# Microcontroller_Stage.net
KiCad netlist of a schematic drawn in Altium Designer
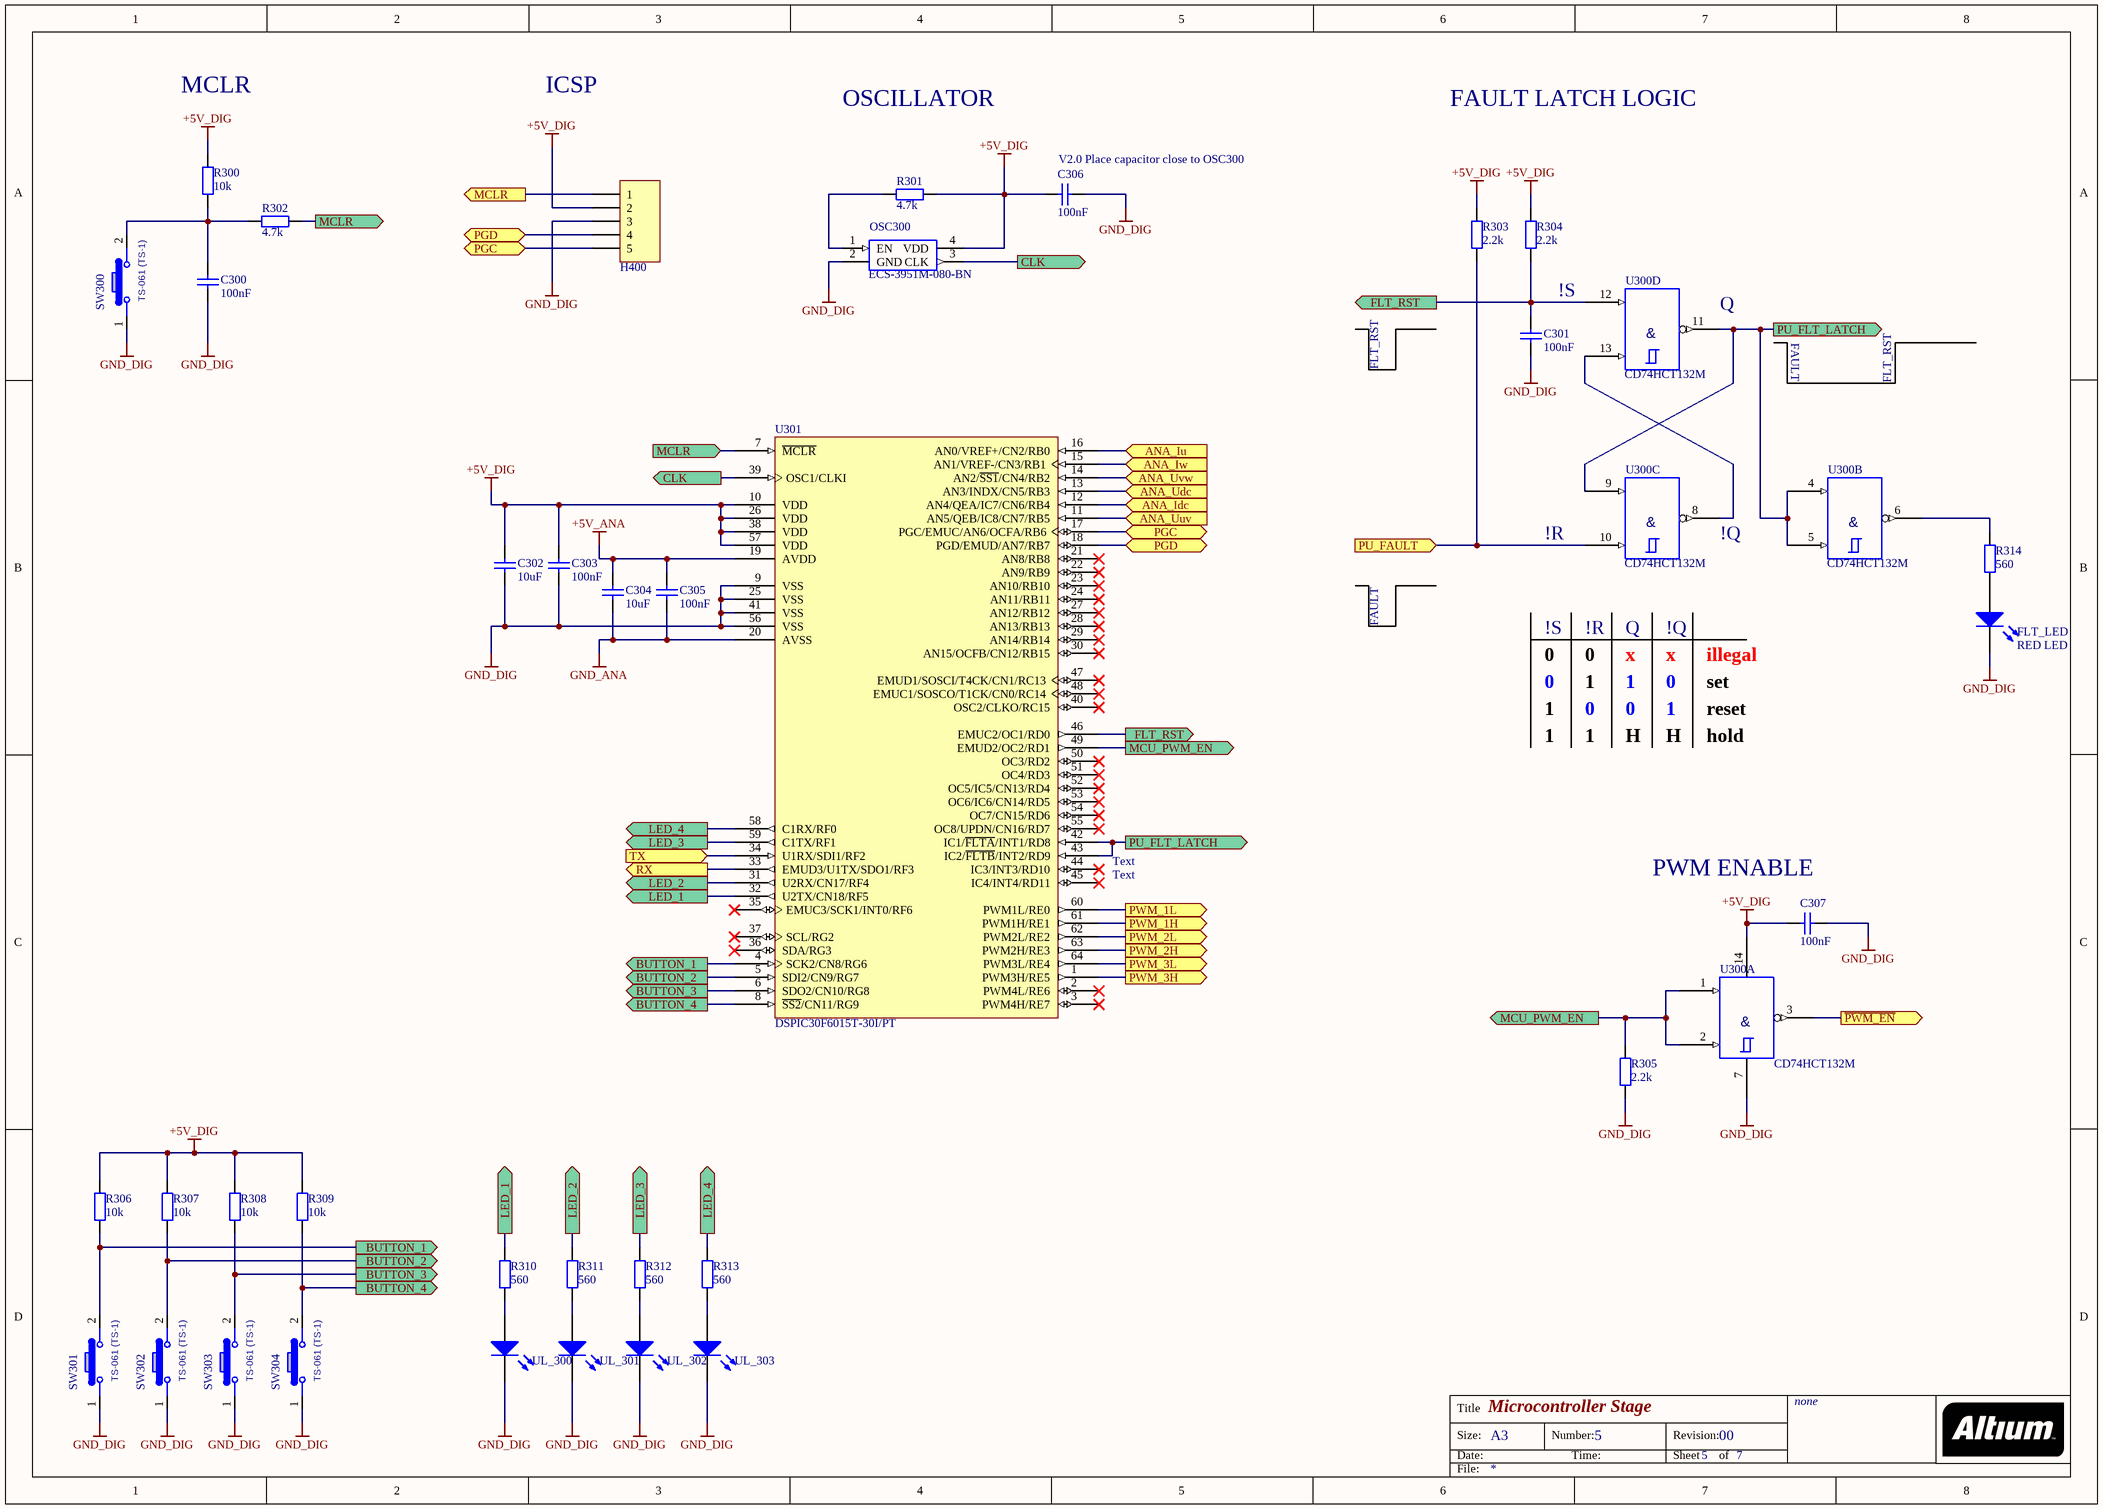
[diagram p0: Microcontroller Stage.SchDoc]

(export (version "E")
  (design (tool "Eeschema 10.0.6"))
  (components
    (comp (ref "C300")
      (value "100nF")
      (footprint "1206_REFLOW")
      (fields (field (name "Comment") "Cap 1206"))
      (libsource (lib "Capacitors") (part "Cap 1206"))
    )
    (comp (ref "C301")
      (value "100nF")
      (footprint "1206_REFLOW")
      (fields (field (name "Comment") "Cap 1206"))
      (libsource (lib "Capacitors") (part "Cap 1206"))
    )
    (comp (ref "C302")
      (value "10uF")
      (footprint "1206_REFLOW")
      (fields (field (name "Comment") "Cap 1206"))
      (libsource (lib "Capacitors") (part "Cap 1206"))
    )
    (comp (ref "C303")
      (value "100nF")
      (footprint "1206_REFLOW")
      (fields (field (name "Comment") "Cap 1206"))
      (libsource (lib "Capacitors") (part "Cap 1206"))
    )
    (comp (ref "C304")
      (value "10uF")
      (footprint "1206_REFLOW")
      (fields (field (name "Comment") "Cap 1206"))
      (libsource (lib "Capacitors") (part "Cap 1206"))
    )
    (comp (ref "C305")
      (value "100nF")
      (footprint "1206_REFLOW")
      (fields (field (name "Comment") "Cap 1206"))
      (libsource (lib "Capacitors") (part "Cap 1206"))
    )
    (comp (ref "C306")
      (value "100nF")
      (footprint "1206_REFLOW")
      (fields (field (name "Comment") "Cap 1206"))
      (libsource (lib "Capacitors") (part "Cap 1206"))
    )
    (comp (ref "C307")
      (value "100nF")
      (footprint "1206_REFLOW")
      (fields (field (name "Comment") "Cap 1206"))
      (libsource (lib "Capacitors") (part "Cap 1206"))
    )
    (comp (ref "FLT_LED") (value "RED LED") (footprint "LED_1206") (libsource (lib "LED") (part "LED")))
    (comp (ref "H400")
      (value "HEADER X5")
      (footprint "SIP5")
      (libsource (lib "Connector") (part "HEADER X5"))
    )
    (comp (ref "OSC300")
      (value "ECS-3951M-080-BN")
      (footprint "OSC7X5")
      (description "ESC-3951M-80-BN 8Mhz")
      (fields (field (name "MFRR PART NO.") "ECS-3951M-080-BN-TR") (field (name "Comment") "ESC-3951M-80-BN"))
      (libsource (lib "Oscillator") (part "ESC-3951M-80-BN"))
    )
    (comp (ref "R300")
      (value "10k")
      (footprint "1206_REFLOW")
      (fields (field (name "Comment") "RES"))
      (libsource (lib "Resistor") (part "RES 1"))
    )
    (comp (ref "R301")
      (value "4.7k")
      (footprint "1206_REFLOW")
      (fields (field (name "Comment") "RES"))
      (libsource (lib "") (part "RES 1_2"))
    )
    (comp (ref "R302")
      (value "4.7k")
      (footprint "1206_REFLOW")
      (fields (field (name "Comment") "RES"))
      (libsource (lib "") (part "RES 1_3"))
    )
    (comp (ref "R303")
      (value "2.2k")
      (footprint "1206_REFLOW")
      (fields (field (name "Comment") "RES"))
      (libsource (lib "Resistor") (part "RES 1"))
    )
    (comp (ref "R304")
      (value "2.2k")
      (footprint "1206_REFLOW")
      (fields (field (name "Comment") "RES"))
      (libsource (lib "Resistor") (part "RES 1"))
    )
    (comp (ref "R305")
      (value "2.2k")
      (footprint "1206_REFLOW")
      (fields (field (name "Comment") "RES"))
      (libsource (lib "Resistor") (part "RES 1"))
    )
    (comp (ref "R306")
      (value "10k")
      (footprint "1206_REFLOW")
      (fields (field (name "Comment") "RES"))
      (libsource (lib "Resistor") (part "RES 1"))
    )
    (comp (ref "R307")
      (value "10k")
      (footprint "1206_REFLOW")
      (fields (field (name "Comment") "RES"))
      (libsource (lib "Resistor") (part "RES 1"))
    )
    (comp (ref "R308")
      (value "10k")
      (footprint "1206_REFLOW")
      (fields (field (name "Comment") "RES"))
      (libsource (lib "Resistor") (part "RES 1"))
    )
    (comp (ref "R309")
      (value "10k")
      (footprint "1206_REFLOW")
      (fields (field (name "Comment") "RES"))
      (libsource (lib "Resistor") (part "RES 1"))
    )
    (comp (ref "R310")
      (value "560")
      (footprint "1206_REFLOW")
      (fields (field (name "Comment") "RES"))
      (libsource (lib "") (part "RES 1_1"))
    )
    (comp (ref "R311")
      (value "560")
      (footprint "1206_REFLOW")
      (fields (field (name "Comment") "RES"))
      (libsource (lib "") (part "RES 1_1"))
    )
    (comp (ref "R312")
      (value "560")
      (footprint "1206_REFLOW")
      (fields (field (name "Comment") "RES"))
      (libsource (lib "") (part "RES 1_1"))
    )
    (comp (ref "R313")
      (value "560")
      (footprint "1206_REFLOW")
      (fields (field (name "Comment") "RES"))
      (libsource (lib "") (part "RES 1_1"))
    )
    (comp (ref "R314")
      (value "560")
      (footprint "1206_REFLOW")
      (fields (field (name "Comment") "RES"))
      (libsource (lib "") (part "RES 1_1"))
    )
    (comp (ref "SW300")
      (value "TS-061 (TS-1)")
      (footprint "BUTTON")
      (description "BUTTON")
      (libsource (lib "Button") (part "TS-061 (TS-1)"))
    )
    (comp (ref "SW301")
      (value "TS-061 (TS-1)")
      (footprint "BUTTON")
      (description "BUTTON")
      (libsource (lib "Button") (part "TS-061 (TS-1)"))
    )
    (comp (ref "SW302")
      (value "TS-061 (TS-1)")
      (footprint "BUTTON")
      (description "BUTTON")
      (libsource (lib "Button") (part "TS-061 (TS-1)"))
    )
    (comp (ref "SW303")
      (value "TS-061 (TS-1)")
      (footprint "BUTTON")
      (description "BUTTON")
      (libsource (lib "Button") (part "TS-061 (TS-1)"))
    )
    (comp (ref "SW304")
      (value "TS-061 (TS-1)")
      (footprint "BUTTON")
      (description "BUTTON")
      (libsource (lib "Button") (part "TS-061 (TS-1)"))
    )
    (comp (ref "U300")
      (value "CD74HCT132M")
      (footprint "SO14")
      (libsource (lib "Logic") (part "CD74HCT132M"))
    )
    (comp (ref "U301")
      (value "DSPIC30F6015T-30I/PT")
      (footprint "TQFP-PT64_N")
      (fields (field (name "PUBLISHER") "Altium Limited"))
      (libsource (lib "Microchip DSC 16-Bit dsPIC30F") (part "DSPIC30F6015T-30I/PT"))
    )
    (comp (ref "UL_300") (value "YELLOW LED") (footprint "LED_1206") (libsource (lib "LED") (part "LED")))
    (comp (ref "UL_301") (value "YELLOW LED") (footprint "LED_1206") (libsource (lib "LED") (part "LED")))
    (comp (ref "UL_302") (value "YELLOW LED") (footprint "LED_1206") (libsource (lib "LED") (part "LED")))
    (comp (ref "UL_303") (value "YELLOW LED") (footprint "LED_1206") (libsource (lib "LED") (part "LED")))
  )
  (nets
    (net (code "1") (name "+5V_ANA") (class "Default")
      (node (ref "C304") (pin "2") (pinfunction "2_2") (pintype "passive"))
      (node (ref "C305") (pin "2") (pinfunction "2_2") (pintype "passive"))
      (node (ref "U301") (pin "19") (pinfunction "AVDD_19") (pintype "power_in"))
    )
    (net (code "2") (name "+5V_DIG") (class "Default")
      (node (ref "C302") (pin "2") (pinfunction "2_2") (pintype "passive"))
      (node (ref "C303") (pin "2") (pinfunction "2_2") (pintype "passive"))
      (node (ref "C306") (pin "1") (pinfunction "1_1") (pintype "passive"))
      (node (ref "C307") (pin "2") (pinfunction "2_2") (pintype "passive"))
      (node (ref "H400") (pin "2") (pinfunction "2_2") (pintype "passive"))
      (node (ref "OSC300") (pin "4") (pinfunction "VDD_4") (pintype "power_in"))
      (node (ref "R300") (pin "1") (pinfunction "1_1") (pintype "passive"))
      (node (ref "R301") (pin "1") (pinfunction "1_1") (pintype "passive"))
      (node (ref "R303") (pin "1") (pinfunction "1_1") (pintype "passive"))
      (node (ref "R304") (pin "1") (pinfunction "1_1") (pintype "passive"))
      (node (ref "R306") (pin "1") (pinfunction "1_1") (pintype "passive"))
      (node (ref "R307") (pin "1") (pinfunction "1_1") (pintype "passive"))
      (node (ref "R308") (pin "1") (pinfunction "1_1") (pintype "passive"))
      (node (ref "R309") (pin "1") (pinfunction "1_1") (pintype "passive"))
      (node (ref "U300") (pin "14") (pinfunction "Vcc_14") (pintype "power_in"))
      (node (ref "U301") (pin "10") (pinfunction "VDD_10") (pintype "power_in"))
      (node (ref "U301") (pin "26") (pinfunction "VDD_26") (pintype "power_in"))
      (node (ref "U301") (pin "38") (pinfunction "VDD_38") (pintype "power_in"))
      (node (ref "U301") (pin "57") (pinfunction "VDD_57") (pintype "power_in"))
    )
    (net (code "3") (name "/ANA_Idc") (class "Default")
      (node (ref "U301") (pin "12") (pinfunction "AN4/QEA/IC7/CN6/RB4_12") (pintype "input"))
    )
    (net (code "4") (name "/ANA_Iu") (class "Default")
      (node (ref "U301") (pin "16") (pinfunction "AN0/VREF+/CN2/RB0_16") (pintype "input"))
    )
    (net (code "5") (name "/ANA_Iw") (class "Default")
      (node (ref "U301") (pin "15") (pinfunction "AN1/VREF-/CN3/RB1_15") (pintype "input"))
    )
    (net (code "6") (name "/ANA_Udc") (class "Default")
      (node (ref "U301") (pin "13") (pinfunction "AN3/INDX/CN5/RB3_13") (pintype "input"))
    )
    (net (code "7") (name "/ANA_Uuv") (class "Default")
      (node (ref "U301") (pin "11") (pinfunction "AN5/QEB/IC8/CN7/RB5_11") (pintype "input"))
    )
    (net (code "8") (name "/ANA_Uvw") (class "Default")
      (node (ref "U301") (pin "14") (pinfunction "AN2/~{SS1}/CN4/RB2_14") (pintype "input"))
    )
    (net (code "9") (name "/BUTTON_1") (class "Default")
      (node (ref "R306") (pin "2") (pinfunction "2_2") (pintype "passive"))
      (node (ref "SW301") (pin "2") (pintype "passive"))
      (node (ref "U301") (pin "4") (pinfunction "SCK2/CN8/RG6_4") (pintype "input"))
    )
    (net (code "10") (name "/BUTTON_2") (class "Default")
      (node (ref "R307") (pin "2") (pinfunction "2_2") (pintype "passive"))
      (node (ref "SW302") (pin "2") (pintype "passive"))
      (node (ref "U301") (pin "5") (pinfunction "SDI2/CN9/RG7_5") (pintype "input"))
    )
    (net (code "11") (name "/BUTTON_3") (class "Default")
      (node (ref "R308") (pin "2") (pinfunction "2_2") (pintype "passive"))
      (node (ref "SW303") (pin "2") (pintype "passive"))
      (node (ref "U301") (pin "6") (pinfunction "SDO2/CN10/RG8_6") (pintype "input"))
    )
    (net (code "12") (name "/BUTTON_4") (class "Default")
      (node (ref "R309") (pin "2") (pinfunction "2_2") (pintype "passive"))
      (node (ref "SW304") (pin "2") (pintype "passive"))
      (node (ref "U301") (pin "8") (pinfunction "~{SS2}/CN11/RG9_8") (pintype "input"))
    )
    (net (code "13") (name "/CLK") (class "Default")
      (node (ref "OSC300") (pin "3") (pinfunction "CLK_3") (pintype "output"))
      (node (ref "U301") (pin "39") (pinfunction "OSC1/CLKI_39") (pintype "input"))
    )
    (net (code "14") (name "/FLT_RST") (class "Default")
      (node (ref "C301") (pin "2") (pinfunction "2_2") (pintype "passive"))
      (node (ref "R304") (pin "2") (pinfunction "2_2") (pintype "passive"))
      (node (ref "U300") (pin "12") (pinfunction "4A_12") (pintype "input"))
      (node (ref "U301") (pin "46") (pinfunction "EMUC2/OC1/RD0_46") (pintype "output"))
    )
    (net (code "15") (name "/LED_1") (class "Default")
      (node (ref "R310") (pin "2") (pinfunction "2_2") (pintype "passive"))
      (node (ref "U301") (pin "32") (pinfunction "U2TX/CN18/RF5_32") (pintype "output"))
    )
    (net (code "16") (name "/LED_2") (class "Default")
      (node (ref "R311") (pin "2") (pinfunction "2_2") (pintype "passive"))
      (node (ref "U301") (pin "31") (pinfunction "U2RX/CN17/RF4_31") (pintype "output"))
    )
    (net (code "17") (name "/LED_3") (class "Default")
      (node (ref "R312") (pin "2") (pinfunction "2_2") (pintype "passive"))
      (node (ref "U301") (pin "59") (pinfunction "C1TX/RF1_59") (pintype "output"))
    )
    (net (code "18") (name "/LED_4") (class "Default")
      (node (ref "R313") (pin "2") (pinfunction "2_2") (pintype "passive"))
      (node (ref "U301") (pin "58") (pinfunction "C1RX/RF0_58") (pintype "output"))
    )
    (net (code "19") (name "/MCLR") (class "Default")
      (node (ref "H400") (pin "1") (pinfunction "1_1") (pintype "passive"))
      (node (ref "R302") (pin "2") (pinfunction "2_2") (pintype "passive"))
      (node (ref "U301") (pin "7") (pinfunction "~{MCLR}_7") (pintype "input"))
    )
    (net (code "20") (name "/MCU_PWM_EN") (class "Default")
      (node (ref "R305") (pin "1") (pinfunction "1_1") (pintype "passive"))
      (node (ref "U300") (pin "1") (pinfunction "1A_1") (pintype "input"))
      (node (ref "U300") (pin "2") (pinfunction "1B_2") (pintype "input"))
      (node (ref "U301") (pin "49") (pinfunction "EMUD2/OC2/RD1_49") (pintype "output"))
    )
    (net (code "21") (name "/PGC") (class "Default")
      (node (ref "H400") (pin "5") (pinfunction "5_5") (pintype "passive"))
      (node (ref "U301") (pin "17") (pinfunction "PGC/EMUC/AN6/OCFA/RB6_17") (pintype "bidirectional"))
    )
    (net (code "22") (name "/PGD") (class "Default")
      (node (ref "H400") (pin "4") (pinfunction "4_4") (pintype "passive"))
      (node (ref "U301") (pin "18") (pinfunction "PGD/EMUD/AN7/RB7_18") (pintype "bidirectional"))
    )
    (net (code "23") (name "/PU_FAULT") (class "Default")
      (node (ref "R303") (pin "2") (pinfunction "2_2") (pintype "passive"))
      (node (ref "U300") (pin "10") (pinfunction "3B_10") (pintype "input"))
    )
    (net (code "24") (name "/PU_FLT_LATCH") (class "Default")
      (node (ref "U300") (pin "11") (pinfunction "~{4Y}_11") (pintype "output"))
      (node (ref "U300") (pin "4") (pinfunction "2A_4") (pintype "input"))
      (node (ref "U300") (pin "5") (pinfunction "2B_5") (pintype "input"))
      (node (ref "U300") (pin "9") (pinfunction "3A_9") (pintype "input"))
      (node (ref "U301") (pin "42") (pinfunction "IC1/~{FLTA}/INT1/RD8_42") (pintype "input"))
      (node (ref "U301") (pin "43") (pinfunction "IC2/~{FLTB}/INT2/RD9_43") (pintype "input"))
    )
    (net (code "25") (name "/PWM_1H") (class "Default")
      (node (ref "U301") (pin "61") (pinfunction "PWM1H/RE1_61") (pintype "output"))
    )
    (net (code "26") (name "/PWM_1L") (class "Default")
      (node (ref "U301") (pin "60") (pinfunction "PWM1L/RE0_60") (pintype "output"))
    )
    (net (code "27") (name "/PWM_2H") (class "Default")
      (node (ref "U301") (pin "63") (pinfunction "PWM2H/RE3_63") (pintype "output"))
    )
    (net (code "28") (name "/PWM_2L") (class "Default")
      (node (ref "U301") (pin "62") (pinfunction "PWM2L/RE2_62") (pintype "output"))
    )
    (net (code "29") (name "/PWM_3H") (class "Default")
      (node (ref "U301") (pin "1") (pinfunction "PWM3H/RE5_1") (pintype "output"))
    )
    (net (code "30") (name "/PWM_3L") (class "Default")
      (node (ref "U301") (pin "64") (pinfunction "PWM3L/RE4_64") (pintype "output"))
    )
    (net (code "31") (name "/RX") (class "Default")
      (node (ref "U301") (pin "33") (pinfunction "EMUD3/U1TX/SDO1/RF3_33") (pintype "output"))
    )
    (net (code "32") (name "/TX") (class "Default")
      (node (ref "U301") (pin "34") (pinfunction "U1RX/SDI1/RF2_34") (pintype "input"))
    )
    (net (code "33") (name "/~{PWM_EN}") (class "Default")
      (node (ref "U300") (pin "3") (pinfunction "~{1Y}_3") (pintype "output"))
    )
    (net (code "34") (name "GND_ANA") (class "Default")
      (node (ref "C304") (pin "1") (pinfunction "1_1") (pintype "passive"))
      (node (ref "C305") (pin "1") (pinfunction "1_1") (pintype "passive"))
      (node (ref "U301") (pin "20") (pinfunction "AVSS_20") (pintype "power_in"))
    )
    (net (code "35") (name "GND_DIG") (class "Default")
      (node (ref "C300") (pin "1") (pinfunction "1_1") (pintype "passive"))
      (node (ref "C301") (pin "1") (pinfunction "1_1") (pintype "passive"))
      (node (ref "C302") (pin "1") (pinfunction "1_1") (pintype "passive"))
      (node (ref "C303") (pin "1") (pinfunction "1_1") (pintype "passive"))
      (node (ref "C306") (pin "2") (pinfunction "2_2") (pintype "passive"))
      (node (ref "C307") (pin "1") (pinfunction "1_1") (pintype "passive"))
      (node (ref "FLT_LED") (pin "K") (pinfunction "K_K") (pintype "passive"))
      (node (ref "H400") (pin "3") (pinfunction "3_3") (pintype "passive"))
      (node (ref "OSC300") (pin "2") (pinfunction "GND_2") (pintype "power_in"))
      (node (ref "R305") (pin "2") (pinfunction "2_2") (pintype "passive"))
      (node (ref "SW300") (pin "1") (pintype "passive"))
      (node (ref "SW301") (pin "1") (pintype "passive"))
      (node (ref "SW302") (pin "1") (pintype "passive"))
      (node (ref "SW303") (pin "1") (pintype "passive"))
      (node (ref "SW304") (pin "1") (pintype "passive"))
      (node (ref "U300") (pin "7") (pinfunction "GND_7") (pintype "power_in"))
      (node (ref "U301") (pin "25") (pinfunction "VSS_25") (pintype "power_in"))
      (node (ref "U301") (pin "41") (pinfunction "VSS_41") (pintype "power_in"))
      (node (ref "U301") (pin "56") (pinfunction "VSS_56") (pintype "power_in"))
      (node (ref "U301") (pin "9") (pinfunction "VSS_9") (pintype "power_in"))
      (node (ref "UL_300") (pin "K") (pinfunction "K_K") (pintype "passive"))
      (node (ref "UL_301") (pin "K") (pinfunction "K_K") (pintype "passive"))
      (node (ref "UL_302") (pin "K") (pinfunction "K_K") (pintype "passive"))
      (node (ref "UL_303") (pin "K") (pinfunction "K_K") (pintype "passive"))
    )
    (net (code "36") (name "Net-(C300-Pad2)") (class "Default")
      (node (ref "C300") (pin "2") (pinfunction "2_2") (pintype "passive"))
      (node (ref "R300") (pin "2") (pinfunction "2_2") (pintype "passive"))
      (node (ref "R302") (pin "1") (pinfunction "1_1") (pintype "passive"))
      (node (ref "SW300") (pin "2") (pintype "passive"))
    )
    (net (code "37") (name "Net-(FLT_LED-PadA)") (class "Default")
      (node (ref "FLT_LED") (pin "A") (pinfunction "A_A") (pintype "passive"))
      (node (ref "R314") (pin "1") (pinfunction "1_1") (pintype "passive"))
    )
    (net (code "38") (name "Net-(OSC300-EN)") (class "Default")
      (node (ref "OSC300") (pin "1") (pinfunction "EN_1") (pintype "input"))
      (node (ref "R301") (pin "2") (pinfunction "2_2") (pintype "passive"))
    )
    (net (code "39") (name "Net-(R310-Pad1)") (class "Default")
      (node (ref "R310") (pin "1") (pinfunction "1_1") (pintype "passive"))
      (node (ref "UL_300") (pin "A") (pinfunction "A_A") (pintype "passive"))
    )
    (net (code "40") (name "Net-(R311-Pad1)") (class "Default")
      (node (ref "R311") (pin "1") (pinfunction "1_1") (pintype "passive"))
      (node (ref "UL_301") (pin "A") (pinfunction "A_A") (pintype "passive"))
    )
    (net (code "41") (name "Net-(R312-Pad1)") (class "Default")
      (node (ref "R312") (pin "1") (pinfunction "1_1") (pintype "passive"))
      (node (ref "UL_302") (pin "A") (pinfunction "A_A") (pintype "passive"))
    )
    (net (code "42") (name "Net-(R313-Pad1)") (class "Default")
      (node (ref "R313") (pin "1") (pinfunction "1_1") (pintype "passive"))
      (node (ref "UL_303") (pin "A") (pinfunction "A_A") (pintype "passive"))
    )
    (net (code "43") (name "Net-(U300B-~{2Y})") (class "Default")
      (node (ref "R314") (pin "2") (pinfunction "2_2") (pintype "passive"))
      (node (ref "U300") (pin "6") (pinfunction "~{2Y}_6") (pintype "output"))
    )
    (net (code "44") (name "Net-(U300C-~{3Y})") (class "Default")
      (node (ref "U300") (pin "13") (pinfunction "4B_13") (pintype "input"))
      (node (ref "U300") (pin "8") (pinfunction "~{3Y}_8") (pintype "output"))
    )
    (net (code "45") (name "unconnected-(SW300-Pad3)") (class "Default")
      (node (ref "SW300") (pin "3") (pintype "passive"))
    )
    (net (code "46") (name "unconnected-(SW300-Pad4)") (class "Default")
      (node (ref "SW300") (pin "4") (pintype "passive"))
    )
    (net (code "47") (name "unconnected-(SW301-Pad3)") (class "Default")
      (node (ref "SW301") (pin "3") (pintype "passive"))
    )
    (net (code "48") (name "unconnected-(SW301-Pad4)") (class "Default")
      (node (ref "SW301") (pin "4") (pintype "passive"))
    )
    (net (code "49") (name "unconnected-(SW302-Pad3)") (class "Default")
      (node (ref "SW302") (pin "3") (pintype "passive"))
    )
    (net (code "50") (name "unconnected-(SW302-Pad4)") (class "Default")
      (node (ref "SW302") (pin "4") (pintype "passive"))
    )
    (net (code "51") (name "unconnected-(SW303-Pad3)") (class "Default")
      (node (ref "SW303") (pin "3") (pintype "passive"))
    )
    (net (code "52") (name "unconnected-(SW303-Pad4)") (class "Default")
      (node (ref "SW303") (pin "4") (pintype "passive"))
    )
    (net (code "53") (name "unconnected-(SW304-Pad3)") (class "Default")
      (node (ref "SW304") (pin "3") (pintype "passive"))
    )
    (net (code "54") (name "unconnected-(SW304-Pad4)") (class "Default")
      (node (ref "SW304") (pin "4") (pintype "passive"))
    )
    (net (code "55") (name "unconnected-(U301-AN8{slash}RB8-Pad21)") (class "Default")
      (node (ref "U301") (pin "21") (pinfunction "AN8/RB8_21") (pintype "bidirectional+no_connect"))
    )
    (net (code "56") (name "unconnected-(U301-AN9{slash}RB9-Pad22)") (class "Default")
      (node (ref "U301") (pin "22") (pinfunction "AN9/RB9_22") (pintype "bidirectional+no_connect"))
    )
    (net (code "57") (name "unconnected-(U301-AN10{slash}RB10-Pad23)") (class "Default")
      (node (ref "U301") (pin "23") (pinfunction "AN10/RB10_23") (pintype "bidirectional+no_connect"))
    )
    (net (code "58") (name "unconnected-(U301-AN11{slash}RB11-Pad24)") (class "Default")
      (node (ref "U301") (pin "24") (pinfunction "AN11/RB11_24") (pintype "bidirectional+no_connect"))
    )
    (net (code "59") (name "unconnected-(U301-AN12{slash}RB12-Pad27)") (class "Default")
      (node (ref "U301") (pin "27") (pinfunction "AN12/RB12_27") (pintype "bidirectional+no_connect"))
    )
    (net (code "60") (name "unconnected-(U301-AN13{slash}RB13-Pad28)") (class "Default")
      (node (ref "U301") (pin "28") (pinfunction "AN13/RB13_28") (pintype "bidirectional+no_connect"))
    )
    (net (code "61") (name "unconnected-(U301-AN14{slash}RB14-Pad29)") (class "Default")
      (node (ref "U301") (pin "29") (pinfunction "AN14/RB14_29") (pintype "bidirectional+no_connect"))
    )
    (net (code "62") (name "unconnected-(U301-AN15{slash}OCFB{slash}CN12{slash}RB15-Pad30)") (class "Default")
      (node (ref "U301") (pin "30") (pinfunction "AN15/OCFB/CN12/RB15_30") (pintype "bidirectional+no_connect"))
    )
    (net (code "63") (name "unconnected-(U301-EMUC1{slash}SOSCO{slash}T1CK{slash}CN0{slash}RC14-Pad48)") (class "Default")
      (node (ref "U301") (pin "48") (pinfunction "EMUC1/SOSCO/T1CK/CN0/RC14_48") (pintype "bidirectional+no_connect"))
    )
    (net (code "64") (name "unconnected-(U301-EMUC3{slash}SCK1{slash}INT0{slash}RF6-Pad35)") (class "Default")
      (node (ref "U301") (pin "35") (pinfunction "EMUC3/SCK1/INT0/RF6_35") (pintype "bidirectional+no_connect"))
    )
    (net (code "65") (name "unconnected-(U301-EMUD1{slash}SOSCI{slash}T4CK{slash}CN1{slash}RC13-Pad47)") (class "Default")
      (node (ref "U301") (pin "47") (pinfunction "EMUD1/SOSCI/T4CK/CN1/RC13_47") (pintype "bidirectional+no_connect"))
    )
    (net (code "66") (name "unconnected-(U301-IC3{slash}INT3{slash}RD10-Pad44)") (class "Default")
      (node (ref "U301") (pin "44") (pinfunction "IC3/INT3/RD10_44") (pintype "bidirectional+no_connect"))
    )
    (net (code "67") (name "unconnected-(U301-IC4{slash}INT4{slash}RD11-Pad45)") (class "Default")
      (node (ref "U301") (pin "45") (pinfunction "IC4/INT4/RD11_45") (pintype "bidirectional+no_connect"))
    )
    (net (code "68") (name "unconnected-(U301-OC3{slash}RD2-Pad50)") (class "Default")
      (node (ref "U301") (pin "50") (pinfunction "OC3/RD2_50") (pintype "bidirectional+no_connect"))
    )
    (net (code "69") (name "unconnected-(U301-OC4{slash}RD3-Pad51)") (class "Default")
      (node (ref "U301") (pin "51") (pinfunction "OC4/RD3_51") (pintype "bidirectional+no_connect"))
    )
    (net (code "70") (name "unconnected-(U301-OC5{slash}IC5{slash}CN13{slash}RD4-Pad52)") (class "Default")
      (node (ref "U301") (pin "52") (pinfunction "OC5/IC5/CN13/RD4_52") (pintype "bidirectional+no_connect"))
    )
    (net (code "71") (name "unconnected-(U301-OC6{slash}IC6{slash}CN14{slash}RD5-Pad53)") (class "Default")
      (node (ref "U301") (pin "53") (pinfunction "OC6/IC6/CN14/RD5_53") (pintype "bidirectional+no_connect"))
    )
    (net (code "72") (name "unconnected-(U301-OC7{slash}CN15{slash}RD6-Pad54)") (class "Default")
      (node (ref "U301") (pin "54") (pinfunction "OC7/CN15/RD6_54") (pintype "bidirectional+no_connect"))
    )
    (net (code "73") (name "unconnected-(U301-OC8{slash}UPDN{slash}CN16{slash}RD7-Pad55)") (class "Default")
      (node (ref "U301") (pin "55") (pinfunction "OC8/UPDN/CN16/RD7_55") (pintype "bidirectional+no_connect"))
    )
    (net (code "74") (name "unconnected-(U301-OSC2{slash}CLKO{slash}RC15-Pad40)") (class "Default")
      (node (ref "U301") (pin "40") (pinfunction "OSC2/CLKO/RC15_40") (pintype "bidirectional+no_connect"))
    )
    (net (code "75") (name "unconnected-(U301-PWM4H{slash}RE7-Pad3)") (class "Default")
      (node (ref "U301") (pin "3") (pinfunction "PWM4H/RE7_3") (pintype "bidirectional+no_connect"))
    )
    (net (code "76") (name "unconnected-(U301-PWM4L{slash}RE6-Pad2)") (class "Default")
      (node (ref "U301") (pin "2") (pinfunction "PWM4L/RE6_2") (pintype "bidirectional+no_connect"))
    )
    (net (code "77") (name "unconnected-(U301-SCL{slash}RG2-Pad37)") (class "Default")
      (node (ref "U301") (pin "37") (pinfunction "SCL/RG2_37") (pintype "bidirectional+no_connect"))
    )
    (net (code "78") (name "unconnected-(U301-SDA{slash}RG3-Pad36)") (class "Default")
      (node (ref "U301") (pin "36") (pinfunction "SDA/RG3_36") (pintype "bidirectional+no_connect"))
    )
  )
)
